# Dual_Motor_Driver.net
KiCad netlist of a schematic drawn in EAGLE
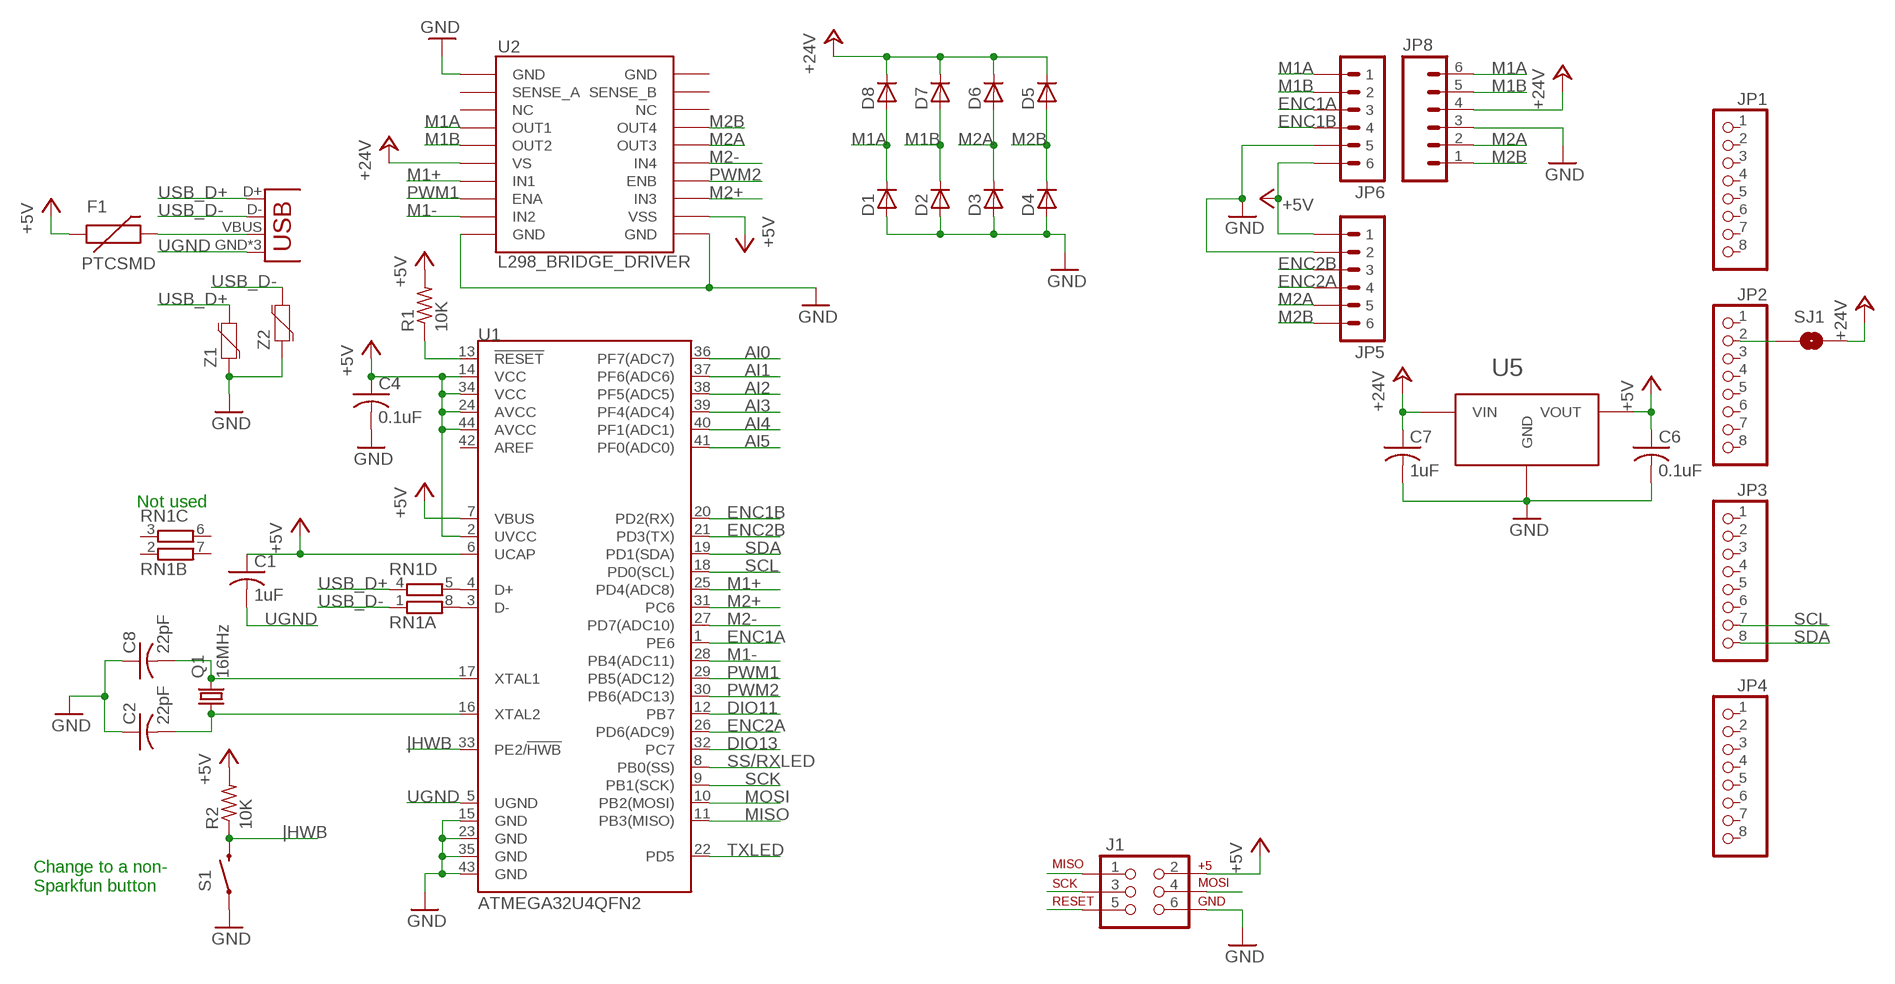
[diagram p0: schematic, sheet 1]

(export (version "E")
  (design (tool "Eeschema 10.0.6"))
  (components
    (comp (ref "C1")
      (value "1uF")
      (footprint "eagle-import:C0603")
      (libsource (lib "eagle-import") (part "C-USC0603"))
    )
    (comp (ref "C2")
      (value "22pF")
      (footprint "eagle-import:C0603")
      (libsource (lib "eagle-import") (part "C-USC0603"))
    )
    (comp (ref "C4")
      (value "0.1uF")
      (footprint "eagle-import:C0603")
      (libsource (lib "eagle-import") (part "C-USC0603"))
    )
    (comp (ref "C6")
      (value "0.1uF")
      (footprint "eagle-import:C0603")
      (libsource (lib "eagle-import") (part "C-USC0603"))
    )
    (comp (ref "C7")
      (value "1uF")
      (footprint "eagle-import:C0603")
      (libsource (lib "eagle-import") (part "C-USC0603"))
    )
    (comp (ref "C8")
      (value "22pF")
      (footprint "eagle-import:C0603")
      (libsource (lib "eagle-import") (part "C-USC0603"))
    )
    (comp (ref "D1")
      (value "D-SOD123")
      (footprint "eagle-import:SOD123")
      (fields (field (name "PART#") "CDBW140-G"))
      (libsource (lib "eagle-import") (part "D-SOD123"))
    )
    (comp (ref "D2")
      (value "D-SOD123")
      (footprint "eagle-import:SOD123")
      (fields (field (name "PART#") "CDBW140-G"))
      (libsource (lib "eagle-import") (part "D-SOD123"))
    )
    (comp (ref "D3")
      (value "D-SOD123")
      (footprint "eagle-import:SOD123")
      (fields (field (name "PART#") "CDBW140-G"))
      (libsource (lib "eagle-import") (part "D-SOD123"))
    )
    (comp (ref "D4")
      (value "D-SOD123")
      (footprint "eagle-import:SOD123")
      (fields (field (name "PART#") "CDBW140-G"))
      (libsource (lib "eagle-import") (part "D-SOD123"))
    )
    (comp (ref "D5")
      (value "D-SOD123")
      (footprint "eagle-import:SOD123")
      (fields (field (name "PART#") "CDBW140-G"))
      (libsource (lib "eagle-import") (part "D-SOD123"))
    )
    (comp (ref "D6")
      (value "D-SOD123")
      (footprint "eagle-import:SOD123")
      (fields (field (name "PART#") "CDBW140-G"))
      (libsource (lib "eagle-import") (part "D-SOD123"))
    )
    (comp (ref "D7")
      (value "D-SOD123")
      (footprint "eagle-import:SOD123")
      (fields (field (name "PART#") "CDBW140-G"))
      (libsource (lib "eagle-import") (part "D-SOD123"))
    )
    (comp (ref "D8")
      (value "D-SOD123")
      (footprint "eagle-import:SOD123")
      (fields (field (name "PART#") "CDBW140-G"))
      (libsource (lib "eagle-import") (part "D-SOD123"))
    )
    (comp (ref "F1")
      (value "PTCSMD")
      (footprint "eagle-import:PTC-1206")
      (fields (field (name "PART#") "0ZCJ0050FF2G"))
      (libsource (lib "eagle-import") (part "PTCSMD"))
    )
    (comp (ref "J1")
      (value "AVR_SPI_PRG_6PTH")
      (footprint "eagle-import:2X3")
      (libsource (lib "eagle-import") (part "AVR_SPI_PRG_6PTH"))
    )
    (comp (ref "JP1")
      (value "PINHD-1X81X08_NO_SILK")
      (footprint "eagle-import:1X08_NO_SS")
      (libsource (lib "eagle-import") (part "PINHD-1X81X08_NO_SILK"))
    )
    (comp (ref "JP2")
      (value "PINHD-1X81X08_NO_SILK")
      (footprint "eagle-import:1X08_NO_SS")
      (libsource (lib "eagle-import") (part "PINHD-1X81X08_NO_SILK"))
    )
    (comp (ref "JP3")
      (value "PINHD-1X81X08_NO_SILK")
      (footprint "eagle-import:1X08_NO_SS")
      (libsource (lib "eagle-import") (part "PINHD-1X81X08_NO_SILK"))
    )
    (comp (ref "JP4")
      (value "PINHD-1X81X08_NO_SILK")
      (footprint "eagle-import:1X08_NO_SS")
      (libsource (lib "eagle-import") (part "PINHD-1X81X08_NO_SILK"))
    )
    (comp (ref "JP5")
      (value "6PIN-SH_RIGHT_ANGLE")
      (footprint "eagle-import:6PIN-SH_SERIES_RA")
      (fields (field (name "PART#") "SM06B-SRSS-TB(LF)(SN)"))
      (libsource (lib "eagle-import") (part "6PIN-SH_RIGHT_ANGLE"))
    )
    (comp (ref "JP6")
      (value "6PIN-SH_RIGHT_ANGLE")
      (footprint "eagle-import:6PIN-SH_SERIES_RA")
      (fields (field (name "PART#") "SM06B-SRSS-TB(LF)(SN)"))
      (libsource (lib "eagle-import") (part "6PIN-SH_RIGHT_ANGLE"))
    )
    (comp (ref "JP7")
      (value "USB-MICROB")
      (footprint "eagle-import:USB-MICROB")
      (libsource (lib "eagle-import") (part "USB-MICROB"))
    )
    (comp (ref "JP8")
      (value "M063.5MM-6")
      (footprint "eagle-import:SCREWTERMINAL-3.5MM-6")
      (libsource (lib "eagle-import") (part "M063.5MM-6"))
    )
    (comp (ref "Q1")
      (value "16MHz")
      (footprint "eagle-import:CTS406")
      (fields (field (name "PART#") "406C35D16M00000"))
      (libsource (lib "eagle-import") (part "CRYSTALCTS406"))
    )
    (comp (ref "R1")
      (value "10K")
      (footprint "eagle-import:R0603")
      (libsource (lib "eagle-import") (part "R-US_R0603"))
    )
    (comp (ref "R2")
      (value "10K")
      (footprint "eagle-import:R0603")
      (libsource (lib "eagle-import") (part "R-US_R0603"))
    )
    (comp (ref "RN1")
      (value "4R-N0603-ARV")
      (footprint "eagle-import:0603-ARV")
      (libsource (lib "eagle-import") (part "4R-N0603-ARV"))
    )
    (comp (ref "S1")
      (value "SWITCH-MOMENTARY-2SMD")
      (footprint "eagle-import:TACTILE_SWITCH_SMD")
      (libsource (lib "eagle-import") (part "SWITCH-MOMENTARY-2SMD"))
    )
    (comp (ref "SJ1")
      (value "SOLDERJUMPERNC")
      (footprint "eagle-import:SJ_2S")
      (libsource (lib "eagle-import") (part "SOLDERJUMPERNC"))
    )
    (comp (ref "U1")
      (value "ATMEGA32U4QFN2")
      (footprint "eagle-import:SPARKFUN-DIGITALIC_QFN-44-NOPAD")
      (libsource (lib "eagle-import") (part "ATMEGA32U4QFN2"))
    )
    (comp (ref "U2")
      (value "L298_BRIDGE_DRIVER")
      (footprint "eagle-import:POWERSO20")
      (libsource (lib "eagle-import") (part "L298_BRIDGE_DRIVER"))
    )
    (comp (ref "U5")
      (value "VOLTAGE-REGULATOR")
      (footprint "eagle-import:SOT89")
      (fields (field (name "PART#") "L78L05ACUTR"))
      (libsource (lib "eagle-import") (part "VOLTAGE-REGULATOR"))
    )
    (comp (ref "Z1")
      (value "VARISTOR-0603")
      (footprint "eagle-import:0603-RES")
      (fields (field (name "PART#") "CG0603MLC-05E"))
      (libsource (lib "eagle-import") (part "VARISTOR-0603"))
    )
    (comp (ref "Z2")
      (value "VARISTOR-0603")
      (footprint "eagle-import:0603-RES")
      (fields (field (name "PART#") "CG0603MLC-05E"))
      (libsource (lib "eagle-import") (part "VARISTOR-0603"))
    )
  )
  (nets
    (net (code "1") (name "+5V") (class "Default")
      (node (ref "C1") (pin "1") (pinfunction "1_1") (pintype "passive"))
      (node (ref "C4") (pin "1") (pinfunction "1_1") (pintype "passive"))
      (node (ref "C6") (pin "1") (pinfunction "1_1") (pintype "passive"))
      (node (ref "F1") (pin "1") (pinfunction "1_1") (pintype "bidirectional"))
      (node (ref "J1") (pin "2") (pinfunction "2_2") (pintype "passive"))
      (node (ref "JP5") (pin "P$1") (pinfunction "1_P$1") (pintype "passive"))
      (node (ref "JP6") (pin "P$6") (pinfunction "6_P$6") (pintype "passive"))
      (node (ref "R1") (pin "2") (pinfunction "2_2") (pintype "passive"))
      (node (ref "R2") (pin "2") (pinfunction "2_2") (pintype "passive"))
      (node (ref "U1") (pin "14") (pinfunction "VCC_14") (pintype "bidirectional"))
      (node (ref "U1") (pin "2") (pinfunction "UVCC_2") (pintype "bidirectional"))
      (node (ref "U1") (pin "24") (pinfunction "AVCC_24") (pintype "bidirectional"))
      (node (ref "U1") (pin "34") (pinfunction "VCC_34") (pintype "bidirectional"))
      (node (ref "U1") (pin "44") (pinfunction "AVCC_44") (pintype "bidirectional"))
      (node (ref "U1") (pin "6") (pinfunction "UCAP_6") (pintype "bidirectional"))
      (node (ref "U1") (pin "7") (pinfunction "VBUS_7") (pintype "bidirectional"))
      (node (ref "U2") (pin "12") (pinfunction "VSS_12") (pintype "bidirectional"))
      (node (ref "U5") (pin "P$1") (pinfunction "VOUT_P$1") (pintype "bidirectional"))
    )
    (net (code "2") (name "+24V") (class "Default")
      (node (ref "C7") (pin "1") (pinfunction "1_1") (pintype "passive"))
      (node (ref "D5") (pin "1") (pinfunction "C_1") (pintype "passive"))
      (node (ref "D6") (pin "1") (pinfunction "C_1") (pintype "passive"))
      (node (ref "D7") (pin "1") (pinfunction "C_1") (pintype "passive"))
      (node (ref "D8") (pin "1") (pinfunction "C_1") (pintype "passive"))
      (node (ref "JP8") (pin "4") (pinfunction "4_4") (pintype "passive"))
      (node (ref "SJ1") (pin "2") (pinfunction "2_2") (pintype "passive"))
      (node (ref "U2") (pin "6") (pinfunction "VS_6") (pintype "bidirectional"))
      (node (ref "U5") (pin "P$3") (pinfunction "VIN_P$3") (pintype "bidirectional"))
    )
    (net (code "3") (name "/AI0") (class "Default")
      (node (ref "U1") (pin "36") (pinfunction "PF7(ADC7)_36") (pintype "bidirectional"))
    )
    (net (code "4") (name "/AI1") (class "Default")
      (node (ref "U1") (pin "37") (pinfunction "PF6(ADC6)_37") (pintype "bidirectional"))
    )
    (net (code "5") (name "/AI2") (class "Default")
      (node (ref "U1") (pin "38") (pinfunction "PF5(ADC5)_38") (pintype "bidirectional"))
    )
    (net (code "6") (name "/AI3") (class "Default")
      (node (ref "U1") (pin "39") (pinfunction "PF4(ADC4)_39") (pintype "bidirectional"))
    )
    (net (code "7") (name "/AI4") (class "Default")
      (node (ref "U1") (pin "40") (pinfunction "PF1(ADC1)_40") (pintype "bidirectional"))
    )
    (net (code "8") (name "/AI5") (class "Default")
      (node (ref "U1") (pin "41") (pinfunction "PF0(ADC0)_41") (pintype "bidirectional"))
    )
    (net (code "9") (name "/DIO11") (class "Default")
      (node (ref "U1") (pin "12") (pinfunction "PB7_12") (pintype "bidirectional"))
    )
    (net (code "10") (name "/DIO13") (class "Default")
      (node (ref "U1") (pin "32") (pinfunction "PC7_32") (pintype "bidirectional"))
    )
    (net (code "11") (name "/ENC1A") (class "Default")
      (node (ref "JP6") (pin "P$3") (pinfunction "3_P$3") (pintype "passive"))
      (node (ref "U1") (pin "1") (pinfunction "PE6_1") (pintype "bidirectional"))
    )
    (net (code "12") (name "/ENC1B") (class "Default")
      (node (ref "JP6") (pin "P$4") (pinfunction "4_P$4") (pintype "passive"))
      (node (ref "U1") (pin "20") (pinfunction "PD2(RX)_20") (pintype "bidirectional"))
    )
    (net (code "13") (name "/ENC2A") (class "Default")
      (node (ref "JP5") (pin "P$4") (pinfunction "4_P$4") (pintype "passive"))
      (node (ref "U1") (pin "26") (pinfunction "PD6(ADC9)_26") (pintype "bidirectional"))
    )
    (net (code "14") (name "/ENC2B") (class "Default")
      (node (ref "JP5") (pin "P$3") (pinfunction "3_P$3") (pintype "passive"))
      (node (ref "U1") (pin "21") (pinfunction "PD3(TX)_21") (pintype "bidirectional"))
    )
    (net (code "15") (name "/M1+") (class "Default")
      (node (ref "U1") (pin "25") (pinfunction "PD4(ADC8)_25") (pintype "bidirectional"))
      (node (ref "U2") (pin "7") (pinfunction "IN1_7") (pintype "bidirectional"))
    )
    (net (code "16") (name "/M1-") (class "Default")
      (node (ref "U1") (pin "28") (pinfunction "PB4(ADC11)_28") (pintype "bidirectional"))
      (node (ref "U2") (pin "9") (pinfunction "IN2_9") (pintype "bidirectional"))
    )
    (net (code "17") (name "/M1A") (class "Default")
      (node (ref "D1") (pin "1") (pinfunction "C_1") (pintype "passive"))
      (node (ref "D8") (pin "2") (pinfunction "A_2") (pintype "passive"))
      (node (ref "JP6") (pin "P$1") (pinfunction "1_P$1") (pintype "passive"))
      (node (ref "JP8") (pin "6") (pinfunction "6_6") (pintype "passive"))
      (node (ref "U2") (pin "4") (pinfunction "OUT1_4") (pintype "bidirectional"))
    )
    (net (code "18") (name "/M1B") (class "Default")
      (node (ref "D2") (pin "1") (pinfunction "C_1") (pintype "passive"))
      (node (ref "D7") (pin "2") (pinfunction "A_2") (pintype "passive"))
      (node (ref "JP6") (pin "P$2") (pinfunction "2_P$2") (pintype "passive"))
      (node (ref "JP8") (pin "5") (pinfunction "5_5") (pintype "passive"))
      (node (ref "U2") (pin "5") (pinfunction "OUT2_5") (pintype "bidirectional"))
    )
    (net (code "19") (name "/M2+") (class "Default")
      (node (ref "U1") (pin "31") (pinfunction "PC6_31") (pintype "bidirectional"))
      (node (ref "U2") (pin "13") (pinfunction "IN3_13") (pintype "bidirectional"))
    )
    (net (code "20") (name "/M2-") (class "Default")
      (node (ref "U1") (pin "27") (pinfunction "PD7(ADC10)_27") (pintype "bidirectional"))
      (node (ref "U2") (pin "15") (pinfunction "IN4_15") (pintype "bidirectional"))
    )
    (net (code "21") (name "/M2A") (class "Default")
      (node (ref "D3") (pin "1") (pinfunction "C_1") (pintype "passive"))
      (node (ref "D6") (pin "2") (pinfunction "A_2") (pintype "passive"))
      (node (ref "JP5") (pin "P$5") (pinfunction "5_P$5") (pintype "passive"))
      (node (ref "JP8") (pin "2") (pinfunction "2_2") (pintype "passive"))
      (node (ref "U2") (pin "16") (pinfunction "OUT3_16") (pintype "bidirectional"))
    )
    (net (code "22") (name "/M2B") (class "Default")
      (node (ref "D4") (pin "1") (pinfunction "C_1") (pintype "passive"))
      (node (ref "D5") (pin "2") (pinfunction "A_2") (pintype "passive"))
      (node (ref "JP5") (pin "P$6") (pinfunction "6_P$6") (pintype "passive"))
      (node (ref "JP8") (pin "1") (pinfunction "1_1") (pintype "passive"))
      (node (ref "U2") (pin "17") (pinfunction "OUT4_17") (pintype "bidirectional"))
    )
    (net (code "23") (name "/MISO") (class "Default")
      (node (ref "J1") (pin "1") (pinfunction "1_1") (pintype "passive"))
      (node (ref "U1") (pin "11") (pinfunction "PB3(MISO)_11") (pintype "bidirectional"))
    )
    (net (code "24") (name "/MOSI") (class "Default")
      (node (ref "J1") (pin "4") (pinfunction "4_4") (pintype "passive"))
      (node (ref "U1") (pin "10") (pinfunction "PB2(MOSI)_10") (pintype "bidirectional"))
    )
    (net (code "25") (name "/PWM1") (class "Default")
      (node (ref "U1") (pin "29") (pinfunction "PB5(ADC12)_29") (pintype "bidirectional"))
      (node (ref "U2") (pin "8") (pinfunction "ENA_8") (pintype "bidirectional"))
    )
    (net (code "26") (name "/PWM2") (class "Default")
      (node (ref "U1") (pin "30") (pinfunction "PB6(ADC13)_30") (pintype "bidirectional"))
      (node (ref "U2") (pin "14") (pinfunction "ENB_14") (pintype "bidirectional"))
    )
    (net (code "27") (name "/RESET") (class "Default")
      (node (ref "J1") (pin "5") (pinfunction "5_5") (pintype "passive"))
      (node (ref "R1") (pin "1") (pinfunction "1_1") (pintype "passive"))
      (node (ref "U1") (pin "13") (pinfunction "~{RESET}_13") (pintype "bidirectional"))
    )
    (net (code "28") (name "/SCK") (class "Default")
      (node (ref "J1") (pin "3") (pinfunction "3_3") (pintype "passive"))
      (node (ref "U1") (pin "9") (pinfunction "PB1(SCK)_9") (pintype "bidirectional"))
    )
    (net (code "29") (name "/SCL") (class "Default")
      (node (ref "JP3") (pin "7") (pinfunction "7_7") (pintype "passive"))
      (node (ref "U1") (pin "18") (pinfunction "PD0(SCL)_18") (pintype "bidirectional"))
    )
    (net (code "30") (name "/SDA") (class "Default")
      (node (ref "JP3") (pin "8") (pinfunction "8_8") (pintype "passive"))
      (node (ref "U1") (pin "19") (pinfunction "PD1(SDA)_19") (pintype "bidirectional"))
    )
    (net (code "31") (name "/SS{slash}RXLED") (class "Default")
      (node (ref "U1") (pin "8") (pinfunction "PB0(SS)_8") (pintype "bidirectional"))
    )
    (net (code "32") (name "/TXLED") (class "Default")
      (node (ref "U1") (pin "22") (pinfunction "PD5_22") (pintype "bidirectional"))
    )
    (net (code "33") (name "/UGND") (class "Default")
      (node (ref "C1") (pin "2") (pinfunction "2_2") (pintype "passive"))
      (node (ref "JP7") (pin "GND") (pinfunction "GND_GND") (pintype "bidirectional"))
      (node (ref "JP7") (pin "MT1") (pinfunction "GND_MT1") (pintype "bidirectional"))
      (node (ref "JP7") (pin "MT2") (pinfunction "GND_MT2") (pintype "bidirectional"))
      (node (ref "U1") (pin "5") (pinfunction "UGND_5") (pintype "bidirectional"))
    )
    (net (code "34") (name "/USB_D+") (class "Default")
      (node (ref "JP7") (pin "D+") (pinfunction "D+_D+") (pintype "bidirectional"))
      (node (ref "RN1") (pin "4") (pinfunction "1_4") (pintype "passive"))
      (node (ref "Z1") (pin "2") (pinfunction "2_2") (pintype "passive"))
    )
    (net (code "35") (name "/USB_D-") (class "Default")
      (node (ref "JP7") (pin "D-") (pinfunction "D-_D-") (pintype "bidirectional"))
      (node (ref "RN1") (pin "1") (pinfunction "1_1") (pintype "passive"))
      (node (ref "Z2") (pin "2") (pinfunction "2_2") (pintype "passive"))
    )
    (net (code "36") (name "/|HWB") (class "Default")
      (node (ref "R2") (pin "1") (pinfunction "1_1") (pintype "passive"))
      (node (ref "S1") (pin "3") (pinfunction "2_3") (pintype "passive"))
      (node (ref "U1") (pin "33") (pinfunction "PE2/~{HWB}_33") (pintype "bidirectional"))
    )
    (net (code "37") (name "GND") (class "Default")
      (node (ref "C2") (pin "1") (pinfunction "1_1") (pintype "passive"))
      (node (ref "C4") (pin "2") (pinfunction "2_2") (pintype "passive"))
      (node (ref "C6") (pin "2") (pinfunction "2_2") (pintype "passive"))
      (node (ref "C7") (pin "2") (pinfunction "2_2") (pintype "passive"))
      (node (ref "C8") (pin "1") (pinfunction "1_1") (pintype "passive"))
      (node (ref "D1") (pin "2") (pinfunction "A_2") (pintype "passive"))
      (node (ref "D2") (pin "2") (pinfunction "A_2") (pintype "passive"))
      (node (ref "D3") (pin "2") (pinfunction "A_2") (pintype "passive"))
      (node (ref "D4") (pin "2") (pinfunction "A_2") (pintype "passive"))
      (node (ref "J1") (pin "6") (pinfunction "6_6") (pintype "passive"))
      (node (ref "JP5") (pin "P$2") (pinfunction "2_P$2") (pintype "passive"))
      (node (ref "JP6") (pin "P$5") (pinfunction "5_P$5") (pintype "passive"))
      (node (ref "JP8") (pin "3") (pinfunction "3_3") (pintype "passive"))
      (node (ref "S1") (pin "1") (pinfunction "1_1") (pintype "passive"))
      (node (ref "U1") (pin "15") (pinfunction "GND_15") (pintype "bidirectional"))
      (node (ref "U1") (pin "23") (pinfunction "GND_23") (pintype "bidirectional"))
      (node (ref "U1") (pin "35") (pinfunction "GND_35") (pintype "bidirectional"))
      (node (ref "U1") (pin "43") (pinfunction "GND_43") (pintype "bidirectional"))
      (node (ref "U2") (pin "1") (pinfunction "GND_1") (pintype "bidirectional"))
      (node (ref "U2") (pin "10") (pinfunction "GND_10") (pintype "bidirectional"))
      (node (ref "U2") (pin "11") (pinfunction "GND_11") (pintype "bidirectional"))
      (node (ref "U5") (pin "P$2") (pinfunction "GND_P$2") (pintype "bidirectional"))
      (node (ref "U5") (pin "P$4") (pinfunction "GND_P$4") (pintype "bidirectional"))
      (node (ref "Z1") (pin "1") (pinfunction "1_1") (pintype "passive"))
      (node (ref "Z2") (pin "1") (pinfunction "1_1") (pintype "passive"))
    )
    (net (code "38") (name "Net-(F1-Pad2)") (class "Default")
      (node (ref "F1") (pin "2") (pinfunction "2_2") (pintype "bidirectional"))
      (node (ref "JP7") (pin "VBUS") (pinfunction "VBUS_VBUS") (pintype "bidirectional"))
    )
    (net (code "39") (name "Net-(JP2-Pad2)") (class "Default")
      (node (ref "JP2") (pin "2") (pinfunction "2_2") (pintype "passive"))
      (node (ref "SJ1") (pin "1") (pinfunction "1_1") (pintype "passive"))
    )
    (net (code "40") (name "Net-(Q1-2)") (class "Default")
      (node (ref "C8") (pin "2") (pinfunction "2_2") (pintype "passive"))
      (node (ref "Q1") (pin "3") (pinfunction "2_3") (pintype "passive"))
      (node (ref "U1") (pin "17") (pinfunction "XTAL1_17") (pintype "bidirectional"))
    )
    (net (code "41") (name "Net-(RN1A-2)") (class "Default")
      (node (ref "RN1") (pin "8") (pinfunction "2_8") (pintype "passive"))
      (node (ref "U1") (pin "3") (pinfunction "D-_3") (pintype "bidirectional"))
    )
    (net (code "42") (name "Net-(RN1D-2)") (class "Default")
      (node (ref "RN1") (pin "5") (pinfunction "2_5") (pintype "passive"))
      (node (ref "U1") (pin "4") (pinfunction "D+_4") (pintype "bidirectional"))
    )
    (net (code "43") (name "Net-(U1-XTAL2)") (class "Default")
      (node (ref "C2") (pin "2") (pinfunction "2_2") (pintype "passive"))
      (node (ref "Q1") (pin "1") (pinfunction "1_1") (pintype "passive"))
      (node (ref "U1") (pin "16") (pinfunction "XTAL2_16") (pintype "bidirectional"))
    )
    (net (code "44") (name "unconnected-(JP1-Pad1)") (class "Default")
      (node (ref "JP1") (pin "1") (pinfunction "1_1") (pintype "passive"))
    )
    (net (code "45") (name "unconnected-(JP1-Pad2)") (class "Default")
      (node (ref "JP1") (pin "2") (pinfunction "2_2") (pintype "passive"))
    )
    (net (code "46") (name "unconnected-(JP1-Pad3)") (class "Default")
      (node (ref "JP1") (pin "3") (pinfunction "3_3") (pintype "passive"))
    )
    (net (code "47") (name "unconnected-(JP1-Pad4)") (class "Default")
      (node (ref "JP1") (pin "4") (pinfunction "4_4") (pintype "passive"))
    )
    (net (code "48") (name "unconnected-(JP1-Pad5)") (class "Default")
      (node (ref "JP1") (pin "5") (pinfunction "5_5") (pintype "passive"))
    )
    (net (code "49") (name "unconnected-(JP1-Pad6)") (class "Default")
      (node (ref "JP1") (pin "6") (pinfunction "6_6") (pintype "passive"))
    )
    (net (code "50") (name "unconnected-(JP1-Pad7)") (class "Default")
      (node (ref "JP1") (pin "7") (pinfunction "7_7") (pintype "passive"))
    )
    (net (code "51") (name "unconnected-(JP1-Pad8)") (class "Default")
      (node (ref "JP1") (pin "8") (pinfunction "8_8") (pintype "passive"))
    )
    (net (code "52") (name "unconnected-(JP2-Pad1)") (class "Default")
      (node (ref "JP2") (pin "1") (pinfunction "1_1") (pintype "passive"))
    )
    (net (code "53") (name "unconnected-(JP2-Pad3)") (class "Default")
      (node (ref "JP2") (pin "3") (pinfunction "3_3") (pintype "passive"))
    )
    (net (code "54") (name "unconnected-(JP2-Pad4)") (class "Default")
      (node (ref "JP2") (pin "4") (pinfunction "4_4") (pintype "passive"))
    )
    (net (code "55") (name "unconnected-(JP2-Pad5)") (class "Default")
      (node (ref "JP2") (pin "5") (pinfunction "5_5") (pintype "passive"))
    )
    (net (code "56") (name "unconnected-(JP2-Pad6)") (class "Default")
      (node (ref "JP2") (pin "6") (pinfunction "6_6") (pintype "passive"))
    )
    (net (code "57") (name "unconnected-(JP2-Pad7)") (class "Default")
      (node (ref "JP2") (pin "7") (pinfunction "7_7") (pintype "passive"))
    )
    (net (code "58") (name "unconnected-(JP2-Pad8)") (class "Default")
      (node (ref "JP2") (pin "8") (pinfunction "8_8") (pintype "passive"))
    )
    (net (code "59") (name "unconnected-(JP3-Pad1)") (class "Default")
      (node (ref "JP3") (pin "1") (pinfunction "1_1") (pintype "passive"))
    )
    (net (code "60") (name "unconnected-(JP3-Pad2)") (class "Default")
      (node (ref "JP3") (pin "2") (pinfunction "2_2") (pintype "passive"))
    )
    (net (code "61") (name "unconnected-(JP3-Pad3)") (class "Default")
      (node (ref "JP3") (pin "3") (pinfunction "3_3") (pintype "passive"))
    )
    (net (code "62") (name "unconnected-(JP3-Pad4)") (class "Default")
      (node (ref "JP3") (pin "4") (pinfunction "4_4") (pintype "passive"))
    )
    (net (code "63") (name "unconnected-(JP3-Pad5)") (class "Default")
      (node (ref "JP3") (pin "5") (pinfunction "5_5") (pintype "passive"))
    )
    (net (code "64") (name "unconnected-(JP3-Pad6)") (class "Default")
      (node (ref "JP3") (pin "6") (pinfunction "6_6") (pintype "passive"))
    )
    (net (code "65") (name "unconnected-(JP4-Pad1)") (class "Default")
      (node (ref "JP4") (pin "1") (pinfunction "1_1") (pintype "passive"))
    )
    (net (code "66") (name "unconnected-(JP4-Pad2)") (class "Default")
      (node (ref "JP4") (pin "2") (pinfunction "2_2") (pintype "passive"))
    )
    (net (code "67") (name "unconnected-(JP4-Pad3)") (class "Default")
      (node (ref "JP4") (pin "3") (pinfunction "3_3") (pintype "passive"))
    )
    (net (code "68") (name "unconnected-(JP4-Pad4)") (class "Default")
      (node (ref "JP4") (pin "4") (pinfunction "4_4") (pintype "passive"))
    )
    (net (code "69") (name "unconnected-(JP4-Pad5)") (class "Default")
      (node (ref "JP4") (pin "5") (pinfunction "5_5") (pintype "passive"))
    )
    (net (code "70") (name "unconnected-(JP4-Pad6)") (class "Default")
      (node (ref "JP4") (pin "6") (pinfunction "6_6") (pintype "passive"))
    )
    (net (code "71") (name "unconnected-(JP4-Pad7)") (class "Default")
      (node (ref "JP4") (pin "7") (pinfunction "7_7") (pintype "passive"))
    )
    (net (code "72") (name "unconnected-(JP4-Pad8)") (class "Default")
      (node (ref "JP4") (pin "8") (pinfunction "8_8") (pintype "passive"))
    )
    (net (code "73") (name "unconnected-(RN1B-1-Pad2)") (class "Default")
      (node (ref "RN1") (pin "2") (pinfunction "1_2") (pintype "passive"))
    )
    (net (code "74") (name "unconnected-(RN1B-2-Pad7)") (class "Default")
      (node (ref "RN1") (pin "7") (pinfunction "2_7") (pintype "passive"))
    )
    (net (code "75") (name "unconnected-(RN1C-1-Pad3)") (class "Default")
      (node (ref "RN1") (pin "3") (pinfunction "1_3") (pintype "passive"))
    )
    (net (code "76") (name "unconnected-(RN1C-2-Pad6)") (class "Default")
      (node (ref "RN1") (pin "6") (pinfunction "2_6") (pintype "passive"))
    )
    (net (code "77") (name "unconnected-(U1-AREF-Pad42)") (class "Default")
      (node (ref "U1") (pin "42") (pinfunction "AREF_42") (pintype "bidirectional"))
    )
    (net (code "78") (name "unconnected-(U2-GND-Pad20)") (class "Default")
      (node (ref "U2") (pin "20") (pinfunction "GND_20") (pintype "bidirectional"))
    )
    (net (code "79") (name "unconnected-(U2-NC-Pad3)") (class "Default")
      (node (ref "U2") (pin "3") (pinfunction "NC_3") (pintype "bidirectional"))
    )
    (net (code "80") (name "unconnected-(U2-NC-Pad18)") (class "Default")
      (node (ref "U2") (pin "18") (pinfunction "NC_18") (pintype "bidirectional"))
    )
    (net (code "81") (name "unconnected-(U2-SENSE_A-Pad2)") (class "Default")
      (node (ref "U2") (pin "2") (pinfunction "SENSE_A_2") (pintype "bidirectional"))
    )
    (net (code "82") (name "unconnected-(U2-SENSE_B-Pad19)") (class "Default")
      (node (ref "U2") (pin "19") (pinfunction "SENSE_B_19") (pintype "bidirectional"))
    )
  )
)
